# Power.net
KiCad netlist of a schematic drawn in Altium Designer
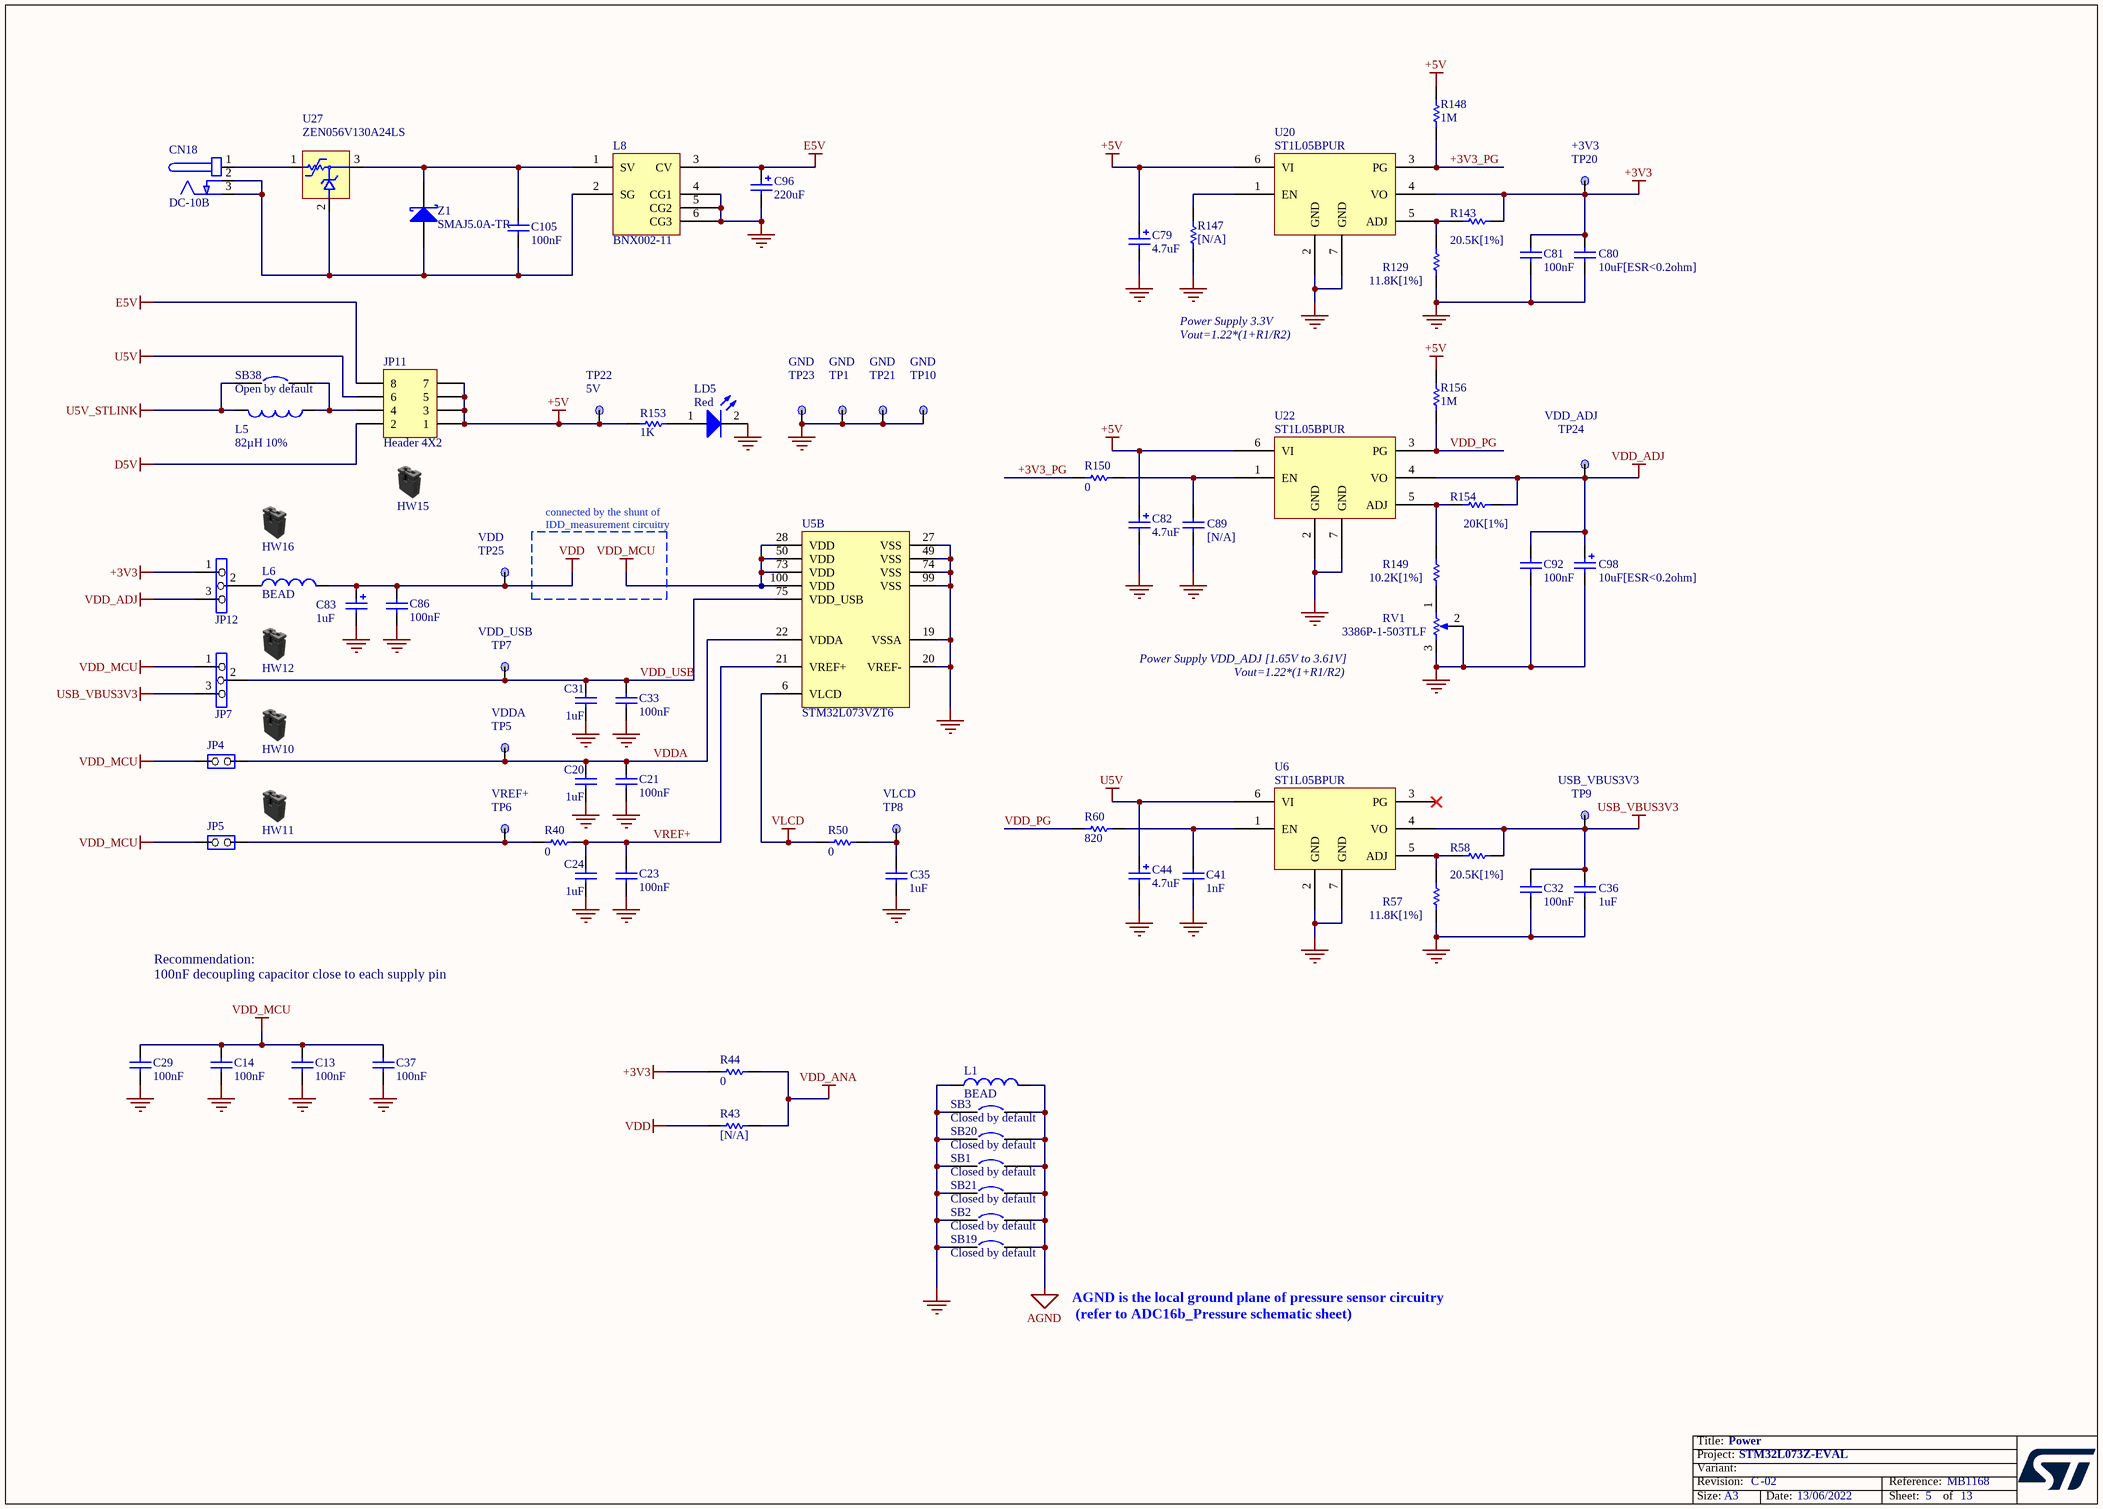
[diagram p0: Power.SchDoc]

(export (version "E")
  (design (tool "Eeschema 10.0.6"))
  (components
    (comp (ref "C13")
      (value "100nF")
      (footprint "0402C")
      (description "Capacitor")
      (fields (field (name "PUBLISHER") "Altium Limited"))
      (libsource (lib "Miscellaneous Devices") (part "CAP"))
    )
    (comp (ref "C14")
      (value "100nF")
      (footprint "0402C")
      (description "Capacitor")
      (fields (field (name "PUBLISHER") "Altium Limited"))
      (libsource (lib "Miscellaneous Devices") (part "CAP"))
    )
    (comp (ref "C20")
      (value "1uF")
      (footprint "0603C")
      (description "Capacitor")
      (fields (field (name "PUBLISHER") "Altium Limited"))
      (libsource (lib "Miscellaneous Devices") (part "CAP"))
    )
    (comp (ref "C21")
      (value "100nF")
      (footprint "0402C")
      (description "Capacitor")
      (fields (field (name "PUBLISHER") "Altium Limited"))
      (libsource (lib "Miscellaneous Devices") (part "Cap"))
    )
    (comp (ref "C23")
      (value "100nF")
      (footprint "0402C")
      (description "Capacitor")
      (fields (field (name "PUBLISHER") "Altium Limited"))
      (libsource (lib "Miscellaneous Devices") (part "Cap"))
    )
    (comp (ref "C24")
      (value "1uF")
      (footprint "0603C")
      (description "Capacitor")
      (fields (field (name "PUBLISHER") "Altium Limited"))
      (libsource (lib "Miscellaneous Devices") (part "CAP"))
    )
    (comp (ref "C29")
      (value "100nF")
      (footprint "0402C")
      (description "Capacitor")
      (fields (field (name "PUBLISHER") "Altium Limited"))
      (libsource (lib "Miscellaneous Devices") (part "CAP"))
    )
    (comp (ref "C31")
      (value "1uF")
      (footprint "0603C")
      (description "Capacitor")
      (fields (field (name "PUBLISHER") "Altium Limited"))
      (libsource (lib "Miscellaneous Devices") (part "CAP"))
    )
    (comp (ref "C32")
      (value "100nF")
      (footprint "0402C")
      (description "Capacitor")
      (fields (field (name "PUBLISHER") "Altium Limited"))
      (libsource (lib "Miscellaneous Devices") (part "Cap"))
    )
    (comp (ref "C33")
      (value "100nF")
      (footprint "0402C")
      (description "Capacitor")
      (fields (field (name "PUBLISHER") "Altium Limited"))
      (libsource (lib "Miscellaneous Devices") (part "Cap"))
    )
    (comp (ref "C35")
      (value "1uF")
      (footprint "0603C")
      (description "Capacitor")
      (fields (field (name "PUBLISHER") "Altium Limited"))
      (libsource (lib "Miscellaneous Devices") (part "CAP"))
    )
    (comp (ref "C36")
      (value "1uF")
      (footprint "0603C")
      (description "Capacitor")
      (fields (field (name "PUBLISHER") "Altium Limited"))
      (libsource (lib "Miscellaneous Devices") (part "Cap"))
    )
    (comp (ref "C37")
      (value "100nF")
      (footprint "0402C")
      (description "Capacitor")
      (fields (field (name "PUBLISHER") "Altium Limited"))
      (libsource (lib "Miscellaneous Devices") (part "CAP"))
    )
    (comp (ref "C41")
      (value "1nF")
      (footprint "0603C")
      (description "Capacitor")
      (fields (field (name "PUBLISHER") "Altium Limited"))
      (libsource (lib "Miscellaneous Devices") (part "Cap"))
    )
    (comp (ref "C44")
      (value "4.7uF")
      (footprint "TAN-A")
      (description "Polarized Capacitor (Radial)")
      (fields (field (name "PUBLISHER") "Altium Limited"))
      (libsource (lib "*") (part "Cap Pol1"))
    )
    (comp (ref "C79")
      (value "4.7uF")
      (footprint "TAN-A")
      (description "Polarized Capacitor (Radial)")
      (fields (field (name "PUBLISHER") "Altium Limited"))
      (libsource (lib "*") (part "Cap Pol1"))
    )
    (comp (ref "C80")
      (value "10uF[ESR<0.2ohm]")
      (footprint "0805C")
      (description "Capacitor")
      (fields (field (name "PUBLISHER") "Altium Limited"))
      (libsource (lib "Miscellaneous Devices") (part "Cap"))
    )
    (comp (ref "C81")
      (value "100nF")
      (footprint "0402C")
      (description "Capacitor")
      (fields (field (name "PUBLISHER") "Altium Limited"))
      (libsource (lib "Miscellaneous Devices") (part "Cap"))
    )
    (comp (ref "C82")
      (value "4.7uF")
      (footprint "TAN-A")
      (description "Polarized Capacitor (Radial)")
      (fields (field (name "PUBLISHER") "Altium Limited"))
      (libsource (lib "*") (part "Cap Pol1"))
    )
    (comp (ref "C83")
      (value "1uF")
      (footprint "TAN-A")
      (description "Polarized Capacitor")
      (fields (field (name "PUBLISHER") "Altium Limited"))
      (libsource (lib "Miscellaneous Devices") (part "Cap Pol1"))
    )
    (comp (ref "C86")
      (value "100nF")
      (footprint "0402C")
      (description "Capacitor")
      (fields (field (name "PUBLISHER") "Altium Limited"))
      (libsource (lib "Miscellaneous Devices") (part "Cap"))
    )
    (comp (ref "C89")
      (value "[N/A]")
      (footprint "0603C")
      (description "Capacitor")
      (fields (field (name "PUBLISHER") "Altium Limited"))
      (libsource (lib "Miscellaneous Devices") (part "cap"))
    )
    (comp (ref "C92")
      (value "100nF")
      (footprint "0402C")
      (description "Capacitor")
      (fields (field (name "PUBLISHER") "Altium Limited"))
      (libsource (lib "Miscellaneous Devices") (part "Cap"))
    )
    (comp (ref "C96")
      (value "220uF")
      (footprint "c310m-6")
      (description "Polarized Capacitor (Radial)")
      (fields (field (name "PUBLISHER") "Altium Limited"))
      (libsource (lib "Miscellaneous Devices") (part "Cap Pol1"))
    )
    (comp (ref "C98")
      (value "10uF[ESR<0.2ohm]")
      (footprint "0805C")
      (description "Polarized Capacitor (Radial)")
      (fields (field (name "PUBLISHER") "Altium Limited"))
      (libsource (lib "Miscellaneous Devices") (part "Cap Pol1"))
    )
    (comp (ref "C105")
      (value "100nF")
      (footprint "0402C")
      (description "Capacitor")
      (fields (field (name "PUBLISHER") "Altium Limited"))
      (libsource (lib "Miscellaneous Devices") (part "CAP"))
    )
    (comp (ref "CN18")
      (value "DC-10B")
      (footprint "PWR_JACK_DC10")
      (libsource (lib "STR910_SCHLIB") (part "PJ202A"))
    )
    (comp (ref "HW10") (value "Shunt Black 2.54mm") (libsource (lib "MB1168") (part "Shunt Black 2.54mm")))
    (comp (ref "HW11") (value "Shunt Black 2.54mm") (libsource (lib "MB1168") (part "Shunt Black 2.54mm")))
    (comp (ref "HW12") (value "Shunt Black 2.54mm") (libsource (lib "MB1168") (part "Shunt Black 2.54mm")))
    (comp (ref "HW15") (value "Shunt Black 2.54mm") (libsource (lib "MB1168") (part "Shunt Black 2.54mm")))
    (comp (ref "HW16") (value "Shunt Black 2.54mm") (libsource (lib "MB1168") (part "Shunt Black 2.54mm")))
    (comp (ref "JP4") (value "~") (footprint "SIP2") (libsource (lib "*") (part "JP2")))
    (comp (ref "JP5") (value "~") (footprint "SIP2") (libsource (lib "*") (part "JP2")))
    (comp (ref "JP7") (value "~") (footprint "SIP3") (libsource (lib "STR910_SCHLIB") (part "Jumper3")))
    (comp (ref "JP11")
      (value "Header 4X2")
      (footprint "HDR_2X4_2R54")
      (description "Header, 4-Pin, Dual row")
      (fields (field (name "PUBLISHER") "Altium Limited"))
      (libsource (lib "Miscellaneous Connectors") (part "Header 4X2"))
    )
    (comp (ref "JP12") (value "~") (footprint "SIP3") (libsource (lib "STR910_SCHLIB") (part "Jumper3")))
    (comp (ref "L1")
      (value "BEAD")
      (footprint "0603L")
      (description "Bead,600R,350mA,0603")
      (fields (field (name "PUBLISHER") "Altium Limited"))
      (libsource (lib "Miscellaneous Devices") (part "Inductor"))
    )
    (comp (ref "L5")
      (value "82µH 10%")
      (footprint "LSM2_4R9X4R9_H4R1")
      (description "Power Inductor 82µH 0,65A")
      (libsource (lib "MCD_TOOLS") (part "Ind_82µH_0.65A_10%"))
    )
    (comp (ref "L6")
      (value "BEAD")
      (footprint "0603L")
      (description "Bead,600R,350mA,0603")
      (fields (field (name "PUBLISHER") "Altium Limited"))
      (libsource (lib "Miscellaneous Devices") (part "Inductor"))
    )
    (comp (ref "L8")
      (value "BNX002-11")
      (footprint "BNX001")
      (libsource (lib "STR910_SCHLIB") (part "BNX002"))
    )
    (comp (ref "LD5")
      (value "Red")
      (footprint "0603D")
      (description "Typical RED, GREEN, YELLOW, AMBER GaAs LED")
      (fields (field (name "PUBLISHER") "Altium Limited"))
      (libsource (lib "Miscellaneous Devices") (part "LED2"))
    )
    (comp (ref "R40")
      (value "0")
      (footprint "0603R")
      (description "Resistor")
      (fields (field (name "PUBLISHER") "Altium Limited"))
      (libsource (lib "Miscellaneous Devices") (part "Res1"))
    )
    (comp (ref "R43")
      (value "[N/A]")
      (footprint "0603R")
      (description "Resistor")
      (fields (field (name "PUBLISHER") "Altium Limited"))
      (libsource (lib "Miscellaneous Devices") (part "res1"))
    )
    (comp (ref "R44")
      (value "0")
      (footprint "0603R")
      (description "Resistor")
      (fields (field (name "PUBLISHER") "Altium Limited"))
      (libsource (lib "Miscellaneous Devices") (part "Res1"))
    )
    (comp (ref "R50")
      (value "0")
      (footprint "0603R")
      (description "Resistor")
      (fields (field (name "PUBLISHER") "Altium Limited"))
      (libsource (lib "Miscellaneous Devices") (part "Res1"))
    )
    (comp (ref "R57")
      (value "11.8K[1%]")
      (footprint "0603R")
      (description "Resistor")
      (fields (field (name "PUBLISHER") "Altium Limited"))
      (libsource (lib "Miscellaneous Devices") (part "Res1"))
    )
    (comp (ref "R58")
      (value "20.5K[1%]")
      (footprint "0603R")
      (description "Resistor")
      (fields (field (name "PUBLISHER") "Altium Limited"))
      (libsource (lib "Miscellaneous Devices") (part "Res1"))
    )
    (comp (ref "R60")
      (value "820")
      (footprint "0603R")
      (description "Resistor")
      (fields (field (name "PUBLISHER") "Altium Limited"))
      (libsource (lib "Miscellaneous Devices") (part "res1"))
    )
    (comp (ref "R129")
      (value "11.8K[1%]")
      (footprint "0603R")
      (description "Resistor")
      (fields (field (name "PUBLISHER") "Altium Limited"))
      (libsource (lib "Miscellaneous Devices") (part "Res1"))
    )
    (comp (ref "R143")
      (value "20.5K[1%]")
      (footprint "0603R")
      (description "Resistor")
      (fields (field (name "PUBLISHER") "Altium Limited"))
      (libsource (lib "Miscellaneous Devices") (part "Res1"))
    )
    (comp (ref "R147")
      (value "[N/A]")
      (footprint "0603R")
      (description "Resistor")
      (fields (field (name "PUBLISHER") "Altium Limited"))
      (libsource (lib "Miscellaneous Devices") (part "res1"))
    )
    (comp (ref "R148")
      (value "1M")
      (footprint "0603R")
      (description "Resistor")
      (fields (field (name "PUBLISHER") "Altium Limited"))
      (libsource (lib "Miscellaneous Devices") (part "res1"))
    )
    (comp (ref "R149")
      (value "10.2K[1%]")
      (footprint "0603R")
      (description "Resistor")
      (fields (field (name "PUBLISHER") "Altium Limited"))
      (libsource (lib "Miscellaneous Devices") (part "Res1"))
    )
    (comp (ref "R150")
      (value "0")
      (footprint "0603R")
      (description "Resistor")
      (fields (field (name "PUBLISHER") "Altium Limited"))
      (libsource (lib "Miscellaneous Devices") (part "res1"))
    )
    (comp (ref "R153")
      (value "1K")
      (footprint "0402R")
      (description "Resistor")
      (fields (field (name "PUBLISHER") "Altium Limited"))
      (libsource (lib "Miscellaneous Devices") (part "res1"))
    )
    (comp (ref "R154")
      (value "20K[1%]")
      (footprint "0603R")
      (description "Resistor")
      (fields (field (name "PUBLISHER") "Altium Limited"))
      (libsource (lib "Miscellaneous Devices") (part "Res1"))
    )
    (comp (ref "R156")
      (value "1M")
      (footprint "0603R")
      (description "Resistor")
      (fields (field (name "PUBLISHER") "Altium Limited"))
      (libsource (lib "Miscellaneous Devices") (part "res1"))
    )
    (comp (ref "RV1")
      (value "3386P-1-503TLF")
      (footprint "3386P")
      (description "Potentiometer 50K")
      (libsource (lib "STR910_SCHLIB") (part "RV"))
    )
    (comp (ref "SB1")
      (value "Closed by default")
      (footprint "SB_0603")
      (description "Circuit Breaker")
      (fields (field (name "PUBLISHER") "Altium Limited"))
      (libsource (lib "Miscellaneous Devices") (part "Circuit Breaker"))
    )
    (comp (ref "SB2")
      (value "Closed by default")
      (footprint "SB_0603")
      (description "Circuit Breaker")
      (fields (field (name "PUBLISHER") "Altium Limited"))
      (libsource (lib "Miscellaneous Devices") (part "Circuit Breaker"))
    )
    (comp (ref "SB3")
      (value "Closed by default")
      (footprint "SB_0603")
      (description "Circuit Breaker")
      (fields (field (name "PUBLISHER") "Altium Limited"))
      (libsource (lib "Miscellaneous Devices") (part "Circuit Breaker"))
    )
    (comp (ref "SB19")
      (value "Closed by default")
      (footprint "SB_0603")
      (description "Circuit Breaker")
      (fields (field (name "PUBLISHER") "Altium Limited"))
      (libsource (lib "Miscellaneous Devices") (part "Circuit Breaker"))
    )
    (comp (ref "SB20")
      (value "Closed by default")
      (footprint "SB_0603")
      (description "Circuit Breaker")
      (fields (field (name "PUBLISHER") "Altium Limited"))
      (libsource (lib "Miscellaneous Devices") (part "Circuit Breaker"))
    )
    (comp (ref "SB21")
      (value "Closed by default")
      (footprint "SB_0603")
      (description "Circuit Breaker")
      (fields (field (name "PUBLISHER") "Altium Limited"))
      (libsource (lib "Miscellaneous Devices") (part "Circuit Breaker"))
    )
    (comp (ref "SB38")
      (value "Open by default")
      (footprint "SB_0603")
      (description "Circuit Breaker")
      (fields (field (name "PUBLISHER") "Altium Limited"))
      (libsource (lib "Miscellaneous Devices") (part "Circuit Breaker"))
    )
    (comp (ref "TP1")
      (value "TP")
      (footprint "TP")
      (fields (field (name "SILKSCREEN") "GND"))
      (libsource (lib "*") (part "TP"))
    )
    (comp (ref "TP5")
      (value "TP")
      (footprint "TP")
      (fields (field (name "SILKSCREEN") "VDDA"))
      (libsource (lib "*") (part "TP"))
    )
    (comp (ref "TP6")
      (value "TP")
      (footprint "TP")
      (fields (field (name "SILKSCREEN") "VREF+"))
      (libsource (lib "*") (part "TP"))
    )
    (comp (ref "TP7")
      (value "TP")
      (footprint "TP")
      (fields (field (name "SILKSCREEN") "VDD_USB"))
      (libsource (lib "*") (part "TP"))
    )
    (comp (ref "TP8")
      (value "TP")
      (footprint "TP")
      (fields (field (name "SILKSCREEN") "VLCD"))
      (libsource (lib "*") (part "TP"))
    )
    (comp (ref "TP9")
      (value "TP")
      (footprint "TP")
      (fields (field (name "SILKSCREEN") "USB_VBUS3V3"))
      (libsource (lib "*") (part "TP"))
    )
    (comp (ref "TP10")
      (value "TP")
      (footprint "TP")
      (fields (field (name "SILKSCREEN") "GND"))
      (libsource (lib "*") (part "TP"))
    )
    (comp (ref "TP20")
      (value "TP")
      (footprint "TP")
      (fields (field (name "SILKSCREEN") "+3V3"))
      (libsource (lib "*") (part "TP"))
    )
    (comp (ref "TP21")
      (value "TP")
      (footprint "TP")
      (fields (field (name "SILKSCREEN") "GND"))
      (libsource (lib "*") (part "TP"))
    )
    (comp (ref "TP22")
      (value "TP")
      (footprint "TP")
      (fields (field (name "SILKSCREEN") "5V"))
      (libsource (lib "*") (part "TP"))
    )
    (comp (ref "TP23")
      (value "TP")
      (footprint "TP")
      (fields (field (name "SILKSCREEN") "GND"))
      (libsource (lib "*") (part "TP"))
    )
    (comp (ref "TP24")
      (value "TP")
      (footprint "TP")
      (fields (field (name "SILKSCREEN") "VDD_ADJ"))
      (libsource (lib "*") (part "TP"))
    )
    (comp (ref "TP25")
      (value "TP")
      (footprint "TP")
      (fields (field (name "SILKSCREEN") "VDD"))
      (libsource (lib "*") (part "TP"))
    )
    (comp (ref "U5")
      (value "STM32L073VZT6")
      (footprint "IC149_100_025_B5")
      (libsource (lib "Almos") (part "BigNemo"))
    )
    (comp (ref "U6")
      (value "ST1L05BPUR")
      (footprint "DFN6_0R95_3X3")
      (libsource (lib "MB1070") (part "ST1L05"))
    )
    (comp (ref "U20")
      (value "ST1L05BPUR")
      (footprint "DFN6_0R95_3X3")
      (libsource (lib "MB1070") (part "ST1L05"))
    )
    (comp (ref "U22")
      (value "ST1L05BPUR")
      (footprint "DFN6_0R95_3X3")
      (libsource (lib "MB1070") (part "ST1L05"))
    )
    (comp (ref "U27")
      (value "ZEN056V130A24LS")
      (footprint "TYCO_ZEN056V130A24LS")
      (libsource (lib "STR910_SCHLIB") (part "ZEN056V130A24LS"))
    )
    (comp (ref "Z1")
      (value "SMAJ5.0A-TR")
      (footprint "sma")
      (description "Schottky Diode")
      (fields (field (name "PUBLISHER") "Altium Limited"))
      (libsource (lib "Miscellaneous Devices") (part "D Schottky"))
    )
  )
  (nets
    (net (code "1") (name "+3V3") (class "Default")
      (node (ref "C80") (pin "1") (pinfunction "1_1") (pintype "passive"))
      (node (ref "C81") (pin "1") (pinfunction "1_1") (pintype "passive"))
      (node (ref "JP12") (pin "1") (pintype "passive"))
      (node (ref "R143") (pin "1") (pinfunction "1_1") (pintype "passive"))
      (node (ref "R44") (pin "1") (pinfunction "1_1") (pintype "passive"))
      (node (ref "TP20") (pin "1") (pinfunction "1_1") (pintype "passive"))
      (node (ref "U20") (pin "4") (pinfunction "VO_4") (pintype "passive"))
    )
    (net (code "2") (name "+5V") (class "Default")
      (node (ref "C79") (pin "1") (pinfunction "1_1") (pintype "passive"))
      (node (ref "C82") (pin "1") (pinfunction "1_1") (pintype "passive"))
      (node (ref "JP11") (pin "1") (pinfunction "1_1") (pintype "passive"))
      (node (ref "JP11") (pin "3") (pinfunction "3_3") (pintype "passive"))
      (node (ref "JP11") (pin "5") (pinfunction "5_5") (pintype "passive"))
      (node (ref "JP11") (pin "7") (pinfunction "7_7") (pintype "passive"))
      (node (ref "R148") (pin "1") (pinfunction "1_1") (pintype "passive"))
      (node (ref "R153") (pin "2") (pinfunction "2_2") (pintype "passive"))
      (node (ref "R156") (pin "1") (pinfunction "1_1") (pintype "passive"))
      (node (ref "TP22") (pin "1") (pinfunction "1_1") (pintype "passive"))
      (node (ref "U20") (pin "6") (pinfunction "VI_6") (pintype "passive"))
      (node (ref "U22") (pin "6") (pinfunction "VI_6") (pintype "passive"))
    )
    (net (code "3") (name "/+3V3_PG") (class "Default")
      (node (ref "R148") (pin "2") (pinfunction "2_2") (pintype "passive"))
      (node (ref "R150") (pin "1") (pinfunction "1_1") (pintype "passive"))
      (node (ref "U20") (pin "3") (pinfunction "PG_3") (pintype "passive"))
    )
    (net (code "4") (name "/VDDA") (class "Default")
      (node (ref "C20") (pin "1") (pinfunction "1_1") (pintype "passive"))
      (node (ref "C21") (pin "2") (pinfunction "2_2") (pintype "passive"))
      (node (ref "JP4") (pin "2") (pinfunction "NO_2") (pintype "passive"))
      (node (ref "TP5") (pin "1") (pinfunction "1_1") (pintype "passive"))
      (node (ref "U5") (pin "22") (pinfunction "VDDA_22") (pintype "passive"))
    )
    (net (code "5") (name "/VDD_PG") (class "Default")
      (node (ref "R156") (pin "2") (pinfunction "2_2") (pintype "passive"))
      (node (ref "R60") (pin "1") (pinfunction "1_1") (pintype "passive"))
      (node (ref "U22") (pin "3") (pinfunction "PG_3") (pintype "passive"))
    )
    (net (code "6") (name "/VDD_USB") (class "Default")
      (node (ref "C31") (pin "1") (pinfunction "1_1") (pintype "passive"))
      (node (ref "C33") (pin "2") (pinfunction "2_2") (pintype "passive"))
      (node (ref "JP7") (pin "2") (pintype "passive"))
      (node (ref "TP7") (pin "1") (pinfunction "1_1") (pintype "passive"))
      (node (ref "U5") (pin "75") (pinfunction "VDD_USB_75") (pintype "passive"))
    )
    (net (code "7") (name "/VREF+") (class "Default")
      (node (ref "C23") (pin "2") (pinfunction "2_2") (pintype "passive"))
      (node (ref "C24") (pin "1") (pinfunction "1_1") (pintype "passive"))
      (node (ref "R40") (pin "2") (pinfunction "2_2") (pintype "passive"))
      (node (ref "U5") (pin "21") (pinfunction "VREF+_21") (pintype "passive"))
    )
    (net (code "8") (name "AGND") (class "Default")
      (node (ref "L1") (pin "2") (pinfunction "2_2") (pintype "passive"))
      (node (ref "SB1") (pin "2") (pinfunction "2_2") (pintype "passive"))
      (node (ref "SB19") (pin "2") (pinfunction "2_2") (pintype "passive"))
      (node (ref "SB2") (pin "2") (pinfunction "2_2") (pintype "passive"))
      (node (ref "SB20") (pin "2") (pinfunction "2_2") (pintype "passive"))
      (node (ref "SB21") (pin "2") (pinfunction "2_2") (pintype "passive"))
      (node (ref "SB3") (pin "2") (pinfunction "2_2") (pintype "passive"))
    )
    (net (code "9") (name "D5V") (class "Default")
      (node (ref "JP11") (pin "2") (pinfunction "2_2") (pintype "passive"))
    )
    (net (code "10") (name "E5V") (class "Default")
      (node (ref "C96") (pin "1") (pinfunction "1_1") (pintype "passive"))
      (node (ref "JP11") (pin "8") (pinfunction "8_8") (pintype "passive"))
      (node (ref "L8") (pin "3") (pinfunction "CV_3") (pintype "passive"))
    )
    (net (code "11") (name "GND") (class "Default")
      (node (ref "C13") (pin "1") (pinfunction "1_1") (pintype "passive"))
      (node (ref "C14") (pin "1") (pinfunction "1_1") (pintype "passive"))
      (node (ref "C20") (pin "2") (pinfunction "2_2") (pintype "passive"))
      (node (ref "C21") (pin "1") (pinfunction "1_1") (pintype "passive"))
      (node (ref "C23") (pin "1") (pinfunction "1_1") (pintype "passive"))
      (node (ref "C24") (pin "2") (pinfunction "2_2") (pintype "passive"))
      (node (ref "C29") (pin "1") (pinfunction "1_1") (pintype "passive"))
      (node (ref "C31") (pin "2") (pinfunction "2_2") (pintype "passive"))
      (node (ref "C32") (pin "2") (pinfunction "2_2") (pintype "passive"))
      (node (ref "C33") (pin "1") (pinfunction "1_1") (pintype "passive"))
      (node (ref "C35") (pin "1") (pinfunction "1_1") (pintype "passive"))
      (node (ref "C36") (pin "2") (pinfunction "2_2") (pintype "passive"))
      (node (ref "C37") (pin "1") (pinfunction "1_1") (pintype "passive"))
      (node (ref "C41") (pin "2") (pinfunction "2_2") (pintype "passive"))
      (node (ref "C44") (pin "2") (pinfunction "2_2") (pintype "passive"))
      (node (ref "C79") (pin "2") (pinfunction "2_2") (pintype "passive"))
      (node (ref "C80") (pin "2") (pinfunction "2_2") (pintype "passive"))
      (node (ref "C81") (pin "2") (pinfunction "2_2") (pintype "passive"))
      (node (ref "C82") (pin "2") (pinfunction "2_2") (pintype "passive"))
      (node (ref "C83") (pin "2") (pinfunction "2_2") (pintype "passive"))
      (node (ref "C86") (pin "1") (pinfunction "1_1") (pintype "passive"))
      (node (ref "C89") (pin "1") (pinfunction "1_1") (pintype "passive"))
      (node (ref "C92") (pin "2") (pinfunction "2_2") (pintype "passive"))
      (node (ref "C96") (pin "2") (pinfunction "2_2") (pintype "passive"))
      (node (ref "C98") (pin "2") (pinfunction "2_2") (pintype "passive"))
      (node (ref "L1") (pin "1") (pinfunction "1_1") (pintype "passive"))
      (node (ref "L8") (pin "4") (pinfunction "CG1_4") (pintype "passive"))
      (node (ref "L8") (pin "5") (pinfunction "CG2_5") (pintype "passive"))
      (node (ref "L8") (pin "6") (pinfunction "CG3_6") (pintype "passive"))
      (node (ref "LD5") (pin "2") (pinfunction "K_2") (pintype "passive"))
      (node (ref "R129") (pin "2") (pinfunction "2_2") (pintype "passive"))
      (node (ref "R147") (pin "2") (pinfunction "2_2") (pintype "passive"))
      (node (ref "R57") (pin "2") (pinfunction "2_2") (pintype "passive"))
      (node (ref "RV1") (pin "2") (pinfunction "TAP_2") (pintype "passive"))
      (node (ref "RV1") (pin "3") (pinfunction "TOP_3") (pintype "passive"))
      (node (ref "SB1") (pin "1") (pinfunction "1_1") (pintype "passive"))
      (node (ref "SB19") (pin "1") (pinfunction "1_1") (pintype "passive"))
      (node (ref "SB2") (pin "1") (pinfunction "1_1") (pintype "passive"))
      (node (ref "SB20") (pin "1") (pinfunction "1_1") (pintype "passive"))
      (node (ref "SB21") (pin "1") (pinfunction "1_1") (pintype "passive"))
      (node (ref "SB3") (pin "1") (pinfunction "1_1") (pintype "passive"))
      (node (ref "TP1") (pin "1") (pinfunction "1_1") (pintype "passive"))
      (node (ref "TP10") (pin "1") (pinfunction "1_1") (pintype "passive"))
      (node (ref "TP21") (pin "1") (pinfunction "1_1") (pintype "passive"))
      (node (ref "TP23") (pin "1") (pinfunction "1_1") (pintype "passive"))
      (node (ref "U20") (pin "2") (pinfunction "GND_2") (pintype "passive"))
      (node (ref "U20") (pin "7") (pinfunction "GND_7") (pintype "passive"))
      (node (ref "U22") (pin "2") (pinfunction "GND_2") (pintype "passive"))
      (node (ref "U22") (pin "7") (pinfunction "GND_7") (pintype "passive"))
      (node (ref "U5") (pin "19") (pinfunction "VSSA_19") (pintype "passive"))
      (node (ref "U5") (pin "20") (pinfunction "VREF-_20") (pintype "passive"))
      (node (ref "U5") (pin "27") (pinfunction "VSS_27") (pintype "passive"))
      (node (ref "U5") (pin "49") (pinfunction "VSS_49") (pintype "passive"))
      (node (ref "U5") (pin "74") (pinfunction "VSS_74") (pintype "passive"))
      (node (ref "U5") (pin "99") (pinfunction "VSS_99") (pintype "passive"))
      (node (ref "U6") (pin "2") (pinfunction "GND_2") (pintype "passive"))
      (node (ref "U6") (pin "7") (pinfunction "GND_7") (pintype "passive"))
    )
    (net (code "12") (name "Net-(C35-Pad2)") (class "Default")
      (node (ref "C35") (pin "2") (pinfunction "2_2") (pintype "passive"))
      (node (ref "R50") (pin "2") (pinfunction "2_2") (pintype "passive"))
      (node (ref "TP8") (pin "1") (pinfunction "1_1") (pintype "passive"))
    )
    (net (code "13") (name "Net-(CN18-+)") (class "Default")
      (node (ref "CN18") (pin "1") (pinfunction "+_1") (pintype "passive"))
      (node (ref "U27") (pin "1") (pintype "passive"))
    )
    (net (code "14") (name "Net-(JP5-NO)") (class "Default")
      (node (ref "JP5") (pin "2") (pinfunction "NO_2") (pintype "passive"))
      (node (ref "R40") (pin "1") (pinfunction "1_1") (pintype "passive"))
      (node (ref "TP6") (pin "1") (pinfunction "1_1") (pintype "passive"))
    )
    (net (code "15") (name "Net-(JP11-Pad4)") (class "Default")
      (node (ref "JP11") (pin "4") (pinfunction "4_4") (pintype "passive"))
      (node (ref "L5") (pin "1") (pinfunction "1_1") (pintype "passive"))
      (node (ref "SB38") (pin "2") (pinfunction "2_2") (pintype "passive"))
    )
    (net (code "16") (name "Net-(JP12-Pad2)") (class "Default")
      (node (ref "JP12") (pin "2") (pintype "passive"))
      (node (ref "L6") (pin "1") (pinfunction "1_1") (pintype "passive"))
    )
    (net (code "17") (name "Net-(L8-SG)") (class "Default")
      (node (ref "C105") (pin "2") (pinfunction "2_2") (pintype "passive"))
      (node (ref "CN18") (pin "2") (pinfunction "GND_2") (pintype "passive"))
      (node (ref "CN18") (pin "3") (pinfunction "GND_3") (pintype "passive"))
      (node (ref "L8") (pin "2") (pinfunction "SG_2") (pintype "passive"))
      (node (ref "U27") (pin "2") (pintype "passive"))
      (node (ref "Z1") (pin "1") (pinfunction "A_1") (pintype "passive"))
    )
    (net (code "18") (name "Net-(L8-SV)") (class "Default")
      (node (ref "C105") (pin "1") (pinfunction "1_1") (pintype "passive"))
      (node (ref "L8") (pin "1") (pinfunction "SV_1") (pintype "passive"))
      (node (ref "U27") (pin "3") (pintype "passive"))
      (node (ref "Z1") (pin "2") (pinfunction "K_2") (pintype "passive"))
    )
    (net (code "19") (name "Net-(LD5-A)") (class "Default")
      (node (ref "LD5") (pin "1") (pinfunction "A_1") (pintype "passive"))
      (node (ref "R153") (pin "1") (pinfunction "1_1") (pintype "passive"))
    )
    (net (code "20") (name "Net-(RV1-BOT)") (class "Default")
      (node (ref "R149") (pin "2") (pinfunction "2_2") (pintype "passive"))
      (node (ref "RV1") (pin "1") (pinfunction "BOT_1") (pintype "passive"))
    )
    (net (code "21") (name "Net-(U6-ADJ)") (class "Default")
      (node (ref "R57") (pin "1") (pinfunction "1_1") (pintype "passive"))
      (node (ref "R58") (pin "2") (pinfunction "2_2") (pintype "passive"))
      (node (ref "U6") (pin "5") (pinfunction "ADJ_5") (pintype "passive"))
    )
    (net (code "22") (name "Net-(U6-EN)") (class "Default")
      (node (ref "C41") (pin "1") (pinfunction "1_1") (pintype "passive"))
      (node (ref "R60") (pin "2") (pinfunction "2_2") (pintype "passive"))
      (node (ref "U6") (pin "1") (pinfunction "EN_1") (pintype "passive"))
    )
    (net (code "23") (name "Net-(U20-ADJ)") (class "Default")
      (node (ref "R129") (pin "1") (pinfunction "1_1") (pintype "passive"))
      (node (ref "R143") (pin "2") (pinfunction "2_2") (pintype "passive"))
      (node (ref "U20") (pin "5") (pinfunction "ADJ_5") (pintype "passive"))
    )
    (net (code "24") (name "Net-(U20-EN)") (class "Default")
      (node (ref "R147") (pin "1") (pinfunction "1_1") (pintype "passive"))
      (node (ref "U20") (pin "1") (pinfunction "EN_1") (pintype "passive"))
    )
    (net (code "25") (name "Net-(U22-ADJ)") (class "Default")
      (node (ref "R149") (pin "1") (pinfunction "1_1") (pintype "passive"))
      (node (ref "R154") (pin "2") (pinfunction "2_2") (pintype "passive"))
      (node (ref "U22") (pin "5") (pinfunction "ADJ_5") (pintype "passive"))
    )
    (net (code "26") (name "Net-(U22-EN)") (class "Default")
      (node (ref "C89") (pin "2") (pinfunction "2_2") (pintype "passive"))
      (node (ref "R150") (pin "2") (pinfunction "2_2") (pintype "passive"))
      (node (ref "U22") (pin "1") (pinfunction "EN_1") (pintype "passive"))
    )
    (net (code "27") (name "U5V") (class "Default")
      (node (ref "C44") (pin "1") (pinfunction "1_1") (pintype "passive"))
      (node (ref "JP11") (pin "6") (pinfunction "6_6") (pintype "passive"))
      (node (ref "U6") (pin "6") (pinfunction "VI_6") (pintype "passive"))
    )
    (net (code "28") (name "U5V_STLINK") (class "Default")
      (node (ref "L5") (pin "2") (pinfunction "2_2") (pintype "passive"))
      (node (ref "SB38") (pin "1") (pinfunction "1_1") (pintype "passive"))
    )
    (net (code "29") (name "USB_VBUS3V3") (class "Default")
      (node (ref "C32") (pin "1") (pinfunction "1_1") (pintype "passive"))
      (node (ref "C36") (pin "1") (pinfunction "1_1") (pintype "passive"))
      (node (ref "JP7") (pin "3") (pintype "passive"))
      (node (ref "R58") (pin "1") (pinfunction "1_1") (pintype "passive"))
      (node (ref "TP9") (pin "1") (pinfunction "1_1") (pintype "passive"))
      (node (ref "U6") (pin "4") (pinfunction "VO_4") (pintype "passive"))
    )
    (net (code "30") (name "VDD") (class "Default")
      (node (ref "C83") (pin "1") (pinfunction "1_1") (pintype "passive"))
      (node (ref "C86") (pin "2") (pinfunction "2_2") (pintype "passive"))
      (node (ref "L6") (pin "2") (pinfunction "2_2") (pintype "passive"))
      (node (ref "R43") (pin "1") (pinfunction "1_1") (pintype "passive"))
      (node (ref "TP25") (pin "1") (pinfunction "1_1") (pintype "passive"))
    )
    (net (code "31") (name "VDD_ADJ") (class "Default")
      (node (ref "C92") (pin "1") (pinfunction "1_1") (pintype "passive"))
      (node (ref "C98") (pin "1") (pinfunction "1_1") (pintype "passive"))
      (node (ref "JP12") (pin "3") (pintype "passive"))
      (node (ref "R154") (pin "1") (pinfunction "1_1") (pintype "passive"))
      (node (ref "TP24") (pin "1") (pinfunction "1_1") (pintype "passive"))
      (node (ref "U22") (pin "4") (pinfunction "VO_4") (pintype "passive"))
    )
    (net (code "32") (name "VDD_ANA") (class "Default")
      (node (ref "R43") (pin "2") (pinfunction "2_2") (pintype "passive"))
      (node (ref "R44") (pin "2") (pinfunction "2_2") (pintype "passive"))
    )
    (net (code "33") (name "VDD_MCU") (class "Default")
      (node (ref "C13") (pin "2") (pinfunction "2_2") (pintype "passive"))
      (node (ref "C14") (pin "2") (pinfunction "2_2") (pintype "passive"))
      (node (ref "C29") (pin "2") (pinfunction "2_2") (pintype "passive"))
      (node (ref "C37") (pin "2") (pinfunction "2_2") (pintype "passive"))
      (node (ref "JP4") (pin "1") (pinfunction "COMMON_1") (pintype "passive"))
      (node (ref "JP5") (pin "1") (pinfunction "COMMON_1") (pintype "passive"))
      (node (ref "JP7") (pin "1") (pintype "passive"))
      (node (ref "U5") (pin "100") (pinfunction "VDD_100") (pintype "passive"))
      (node (ref "U5") (pin "28") (pinfunction "VDD_28") (pintype "passive"))
      (node (ref "U5") (pin "50") (pinfunction "VDD_50") (pintype "passive"))
      (node (ref "U5") (pin "73") (pinfunction "VDD_73") (pintype "passive"))
    )
    (net (code "34") (name "VLCD") (class "Default")
      (node (ref "R50") (pin "1") (pinfunction "1_1") (pintype "passive"))
      (node (ref "U5") (pin "6") (pinfunction "VLCD_6") (pintype "passive"))
    )
    (net (code "35") (name "unconnected-(U6-PG-Pad3)") (class "Default")
      (node (ref "U6") (pin "3") (pinfunction "PG_3") (pintype "passive+no_connect"))
    )
  )
)
